# Qwiic_SAO.net
KiCad netlist of a schematic drawn in EAGLE
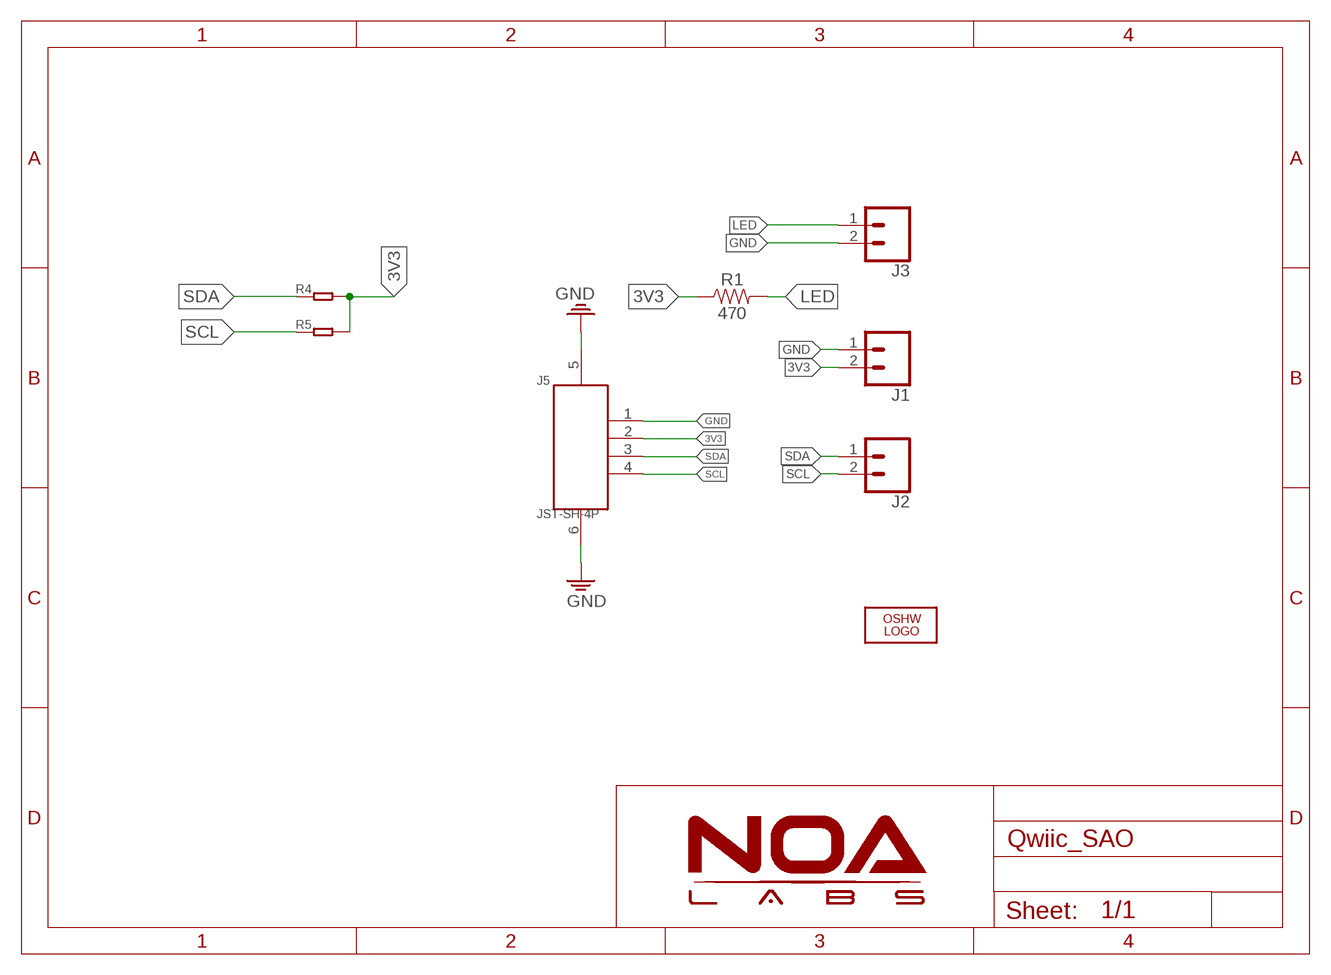
[diagram p0: schematic, sheet 1]

(export (version "E")
  (design (tool "Eeschema 10.0.6"))
  (components
    (comp (ref "J1")
      (value "CONN_02")
      (footprint "eagle-import:1X02")
      (libsource (lib "eagle-import") (part "CONN_02"))
    )
    (comp (ref "J2")
      (value "CONN_02")
      (footprint "eagle-import:1X02")
      (libsource (lib "eagle-import") (part "CONN_02"))
    )
    (comp (ref "J3")
      (value "CONN_02")
      (footprint "eagle-import:1X02")
      (libsource (lib "eagle-import") (part "CONN_02"))
    )
    (comp (ref "J5")
      (value "JST-SH-4P")
      (footprint "eagle-import:SM04B-SRSS-TB")
      (libsource (lib "eagle-import") (part "JST-SH-4P"))
    )
    (comp (ref "LOGO1")
      (value "LOGO-OSHW-6MILX0070-NT")
      (footprint "eagle-import:OSHW_6X70_NOTEXT")
      (libsource (lib "eagle-import") (part "LOGO-OSHW-6MILX0070-NT"))
    )
    (comp (ref "R1")
      (value "470")
      (footprint "eagle-import:0603")
      (libsource (lib "eagle-import") (part "470OHM-0603-1/10W-1%"))
    )
    (comp (ref "R4")
      (value "R-0603")
      (footprint "eagle-import:R0603")
      (libsource (lib "eagle-import") (part "R-0603"))
    )
    (comp (ref "R5")
      (value "R-0603")
      (footprint "eagle-import:R0603")
      (libsource (lib "eagle-import") (part "R-0603"))
    )
  )
  (nets
    (net (code "1") (name "3V3") (class "Default")
      (node (ref "J1") (pin "2") (pinfunction "2_2") (pintype "passive"))
      (node (ref "J5") (pin "2") (pinfunction "2_2") (pintype "bidirectional"))
      (node (ref "R1") (pin "1") (pinfunction "1_1") (pintype "passive"))
      (node (ref "R4") (pin "2") (pinfunction "2_2") (pintype "passive"))
      (node (ref "R5") (pin "2") (pinfunction "2_2") (pintype "passive"))
    )
    (net (code "2") (name "GND") (class "Default")
      (node (ref "J1") (pin "1") (pinfunction "1_1") (pintype "passive"))
      (node (ref "J3") (pin "2") (pinfunction "2_2") (pintype "passive"))
      (node (ref "J5") (pin "1") (pinfunction "1_1") (pintype "bidirectional"))
      (node (ref "J5") (pin "5") (pinfunction "5_5") (pintype "bidirectional"))
      (node (ref "J5") (pin "6") (pinfunction "6_6") (pintype "bidirectional"))
    )
    (net (code "3") (name "LED") (class "Default")
      (node (ref "J3") (pin "1") (pinfunction "1_1") (pintype "passive"))
      (node (ref "R1") (pin "2") (pinfunction "2_2") (pintype "passive"))
    )
    (net (code "4") (name "SCL") (class "Default")
      (node (ref "J2") (pin "2") (pinfunction "2_2") (pintype "passive"))
      (node (ref "J5") (pin "4") (pinfunction "4_4") (pintype "bidirectional"))
      (node (ref "R5") (pin "1") (pinfunction "1_1") (pintype "passive"))
    )
    (net (code "5") (name "SDA") (class "Default")
      (node (ref "J2") (pin "1") (pinfunction "1_1") (pintype "passive"))
      (node (ref "J5") (pin "3") (pinfunction "3_3") (pintype "bidirectional"))
      (node (ref "R4") (pin "1") (pinfunction "1_1") (pintype "passive"))
    )
  )
)
